# LV25-P_380Vac_ADC.net
KiCad netlist of a schematic drawn in Altium Designer
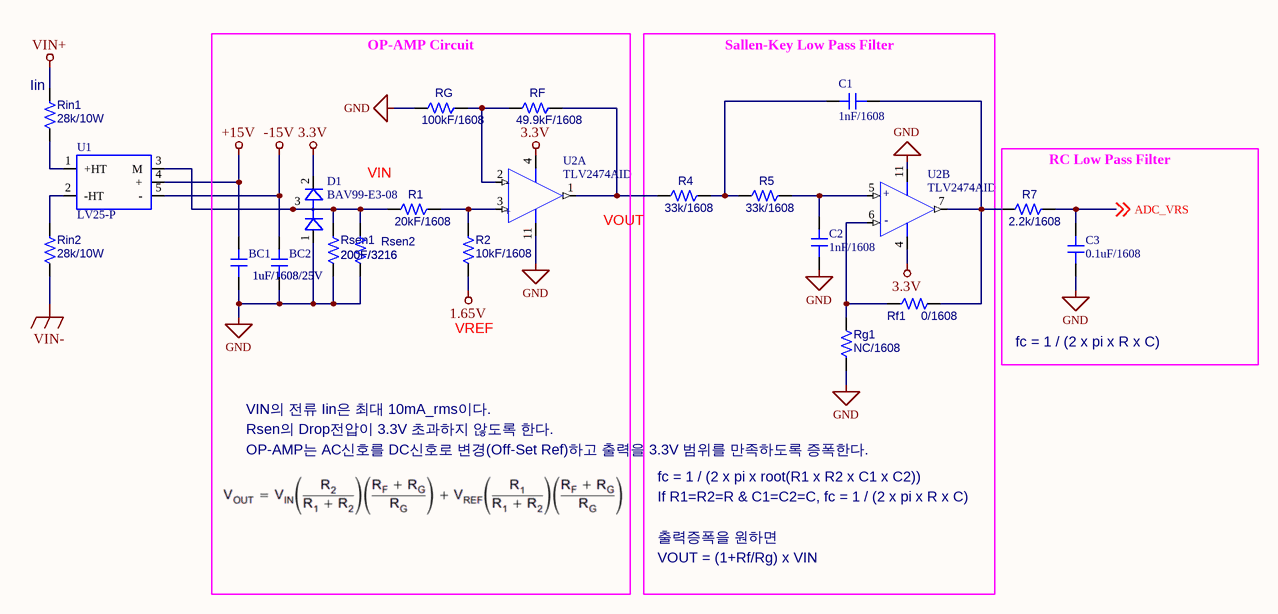
[diagram p0: LV25-P 380Vac ADC 센싱회로.SchDoc]

(export (version "E")
  (design (tool "Eeschema 10.0.6"))
  (components
    (comp (ref "BC1")
      (value "1uF/1608/25V")
      (footprint "C-1608")
      (libsource (lib "*") (part "CAPACITOR NON-POL_1"))
    )
    (comp (ref "BC2")
      (value "1uF/1608/25V")
      (footprint "C-1608")
      (libsource (lib "*") (part "CAPACITOR NON-POL_1"))
    )
    (comp (ref "C1")
      (value "1nF/1608")
      (footprint "C-1608")
      (libsource (lib "*") (part "CAPACITOR NON-POL_1"))
    )
    (comp (ref "C2")
      (value "1nF/1608")
      (footprint "C-1608")
      (libsource (lib "*") (part "CAPACITOR NON-POL_1"))
    )
    (comp (ref "C3")
      (value "0.1uF/1608")
      (footprint "C-1608")
      (libsource (lib "*") (part "CAPACITOR NON-POL_1"))
    )
    (comp (ref "D1")
      (value "BAV99-E3-08")
      (footprint "SOT-23")
      (description "DIODE ARRAY GP 70V 150MA SOT23")
      (libsource (lib "Schlib1_BAV99") (part "BAV99-E3-08"))
    )
    (comp (ref "R1") (value "20kF/1608") (footprint "R-1608") (libsource (lib "*") (part "R_Dup1")))
    (comp (ref "R2") (value "10kF/1608") (footprint "R-1608") (libsource (lib "*") (part "R_Dup1")))
    (comp (ref "R4") (value "33k/1608") (footprint "R-1608") (libsource (lib "*") (part "R_Dup1")))
    (comp (ref "R5") (value "33k/1608") (footprint "R-1608") (libsource (lib "*") (part "R_Dup1")))
    (comp (ref "R7") (value "2.2k/1608") (footprint "R-1608") (libsource (lib "*") (part "R_Dup1")))
    (comp (ref "RF") (value "49.9kF/1608") (footprint "R-1608") (libsource (lib "*") (part "R_Dup1")))
    (comp (ref "Rf1") (value "0/1608") (footprint "R-1608") (libsource (lib "*") (part "R_Dup1")))
    (comp (ref "RG") (value "100kF/1608") (footprint "R-1608") (libsource (lib "*") (part "R_Dup1")))
    (comp (ref "Rg1") (value "NC/1608") (footprint "R-1608") (libsource (lib "*") (part "R_Dup1")))
    (comp (ref "Rin1") (value "28k/10W") (footprint "R-1608") (libsource (lib "*") (part "R_Dup1")))
    (comp (ref "Rin2") (value "28k/10W") (footprint "R-1608") (libsource (lib "*") (part "R_Dup1")))
    (comp (ref "Rsen1") (value "200F/3216") (footprint "R-1608") (libsource (lib "*") (part "R_Dup1")))
    (comp (ref "Rsen2") (value "200F/3216") (footprint "R-1608") (libsource (lib "*") (part "R_Dup1")))
    (comp (ref "U1") (value "LV25-P") (libsource (lib "SysInTeck_SchLib1") (part "LV25-P")))
    (comp (ref "U2") (value "TLV2474AID") (footprint "SO-14") (libsource (lib "*") (part "OPA4336_1")))
  )
  (nets
    (net (code "1") (name "+15V") (class "Default")
      (node (ref "BC1") (pin "1") (pinfunction "1_1") (pintype "passive"))
      (node (ref "U1") (pin "4") (pinfunction "+_4") (pintype "passive"))
    )
    (net (code "2") (name "-15V") (class "Default")
      (node (ref "BC2") (pin "1") (pinfunction "1_1") (pintype "passive"))
      (node (ref "U1") (pin "5") (pinfunction "-_5") (pintype "passive"))
    )
    (net (code "3") (name "1.65V") (class "Default")
      (node (ref "R2") (pin "2") (pinfunction "2_2") (pintype "passive"))
    )
    (net (code "4") (name "3.3V") (class "Default")
      (node (ref "D1") (pin "2") (pinfunction "2_2") (pintype "passive"))
      (node (ref "U2") (pin "4") (pinfunction "+VCC_4") (pintype "power_in"))
    )
    (net (code "5") (name "ADC_VRS") (class "Default")
      (node (ref "C3") (pin "1") (pinfunction "1_1") (pintype "passive"))
      (node (ref "R7") (pin "1") (pinfunction "1_1") (pintype "passive"))
    )
    (net (code "6") (name "GND") (class "Default")
      (node (ref "BC1") (pin "2") (pinfunction "2_2") (pintype "passive"))
      (node (ref "BC2") (pin "2") (pinfunction "2_2") (pintype "passive"))
      (node (ref "C2") (pin "2") (pinfunction "2_2") (pintype "passive"))
      (node (ref "C3") (pin "2") (pinfunction "2_2") (pintype "passive"))
      (node (ref "D1") (pin "1") (pinfunction "1_1") (pintype "passive"))
      (node (ref "RG") (pin "2") (pinfunction "2_2") (pintype "passive"))
      (node (ref "Rg1") (pin "1") (pinfunction "1_1") (pintype "passive"))
      (node (ref "Rsen1") (pin "2") (pinfunction "2_2") (pintype "passive"))
      (node (ref "Rsen2") (pin "2") (pinfunction "2_2") (pintype "passive"))
      (node (ref "U2") (pin "11") (pinfunction "-VCC_11") (pintype "power_in"))
    )
    (net (code "7") (name "Net-(C1-Pad1)") (class "Default")
      (node (ref "C1") (pin "1") (pinfunction "1_1") (pintype "passive"))
      (node (ref "R4") (pin "1") (pinfunction "1_1") (pintype "passive"))
      (node (ref "R5") (pin "2") (pinfunction "2_2") (pintype "passive"))
    )
    (net (code "8") (name "Net-(U1-+HT)") (class "Default")
      (node (ref "Rin1") (pin "2") (pinfunction "2_2") (pintype "passive"))
      (node (ref "U1") (pin "1") (pinfunction "+HT_1") (pintype "passive"))
    )
    (net (code "9") (name "Net-(U1--HT)") (class "Default")
      (node (ref "Rin2") (pin "1") (pinfunction "1_1") (pintype "passive"))
      (node (ref "U1") (pin "2") (pinfunction "-HT_2") (pintype "passive"))
    )
    (net (code "10") (name "Net-(U1-M)") (class "Default")
      (node (ref "D1") (pin "3") (pinfunction "3_3") (pintype "passive"))
      (node (ref "R1") (pin "2") (pinfunction "2_2") (pintype "passive"))
      (node (ref "Rsen1") (pin "1") (pinfunction "1_1") (pintype "passive"))
      (node (ref "Rsen2") (pin "1") (pinfunction "1_1") (pintype "passive"))
      (node (ref "U1") (pin "3") (pinfunction "M_3") (pintype "passive"))
    )
    (net (code "11") (name "Net-(U2A-+IN)") (class "Default")
      (node (ref "R1") (pin "1") (pinfunction "1_1") (pintype "passive"))
      (node (ref "R2") (pin "1") (pinfunction "1_1") (pintype "passive"))
      (node (ref "U2") (pin "3") (pinfunction "+IN_3") (pintype "input"))
    )
    (net (code "12") (name "Net-(U2A--IN)") (class "Default")
      (node (ref "RF") (pin "2") (pinfunction "2_2") (pintype "passive"))
      (node (ref "RG") (pin "1") (pinfunction "1_1") (pintype "passive"))
      (node (ref "U2") (pin "2") (pinfunction "-IN_2") (pintype "input"))
    )
    (net (code "13") (name "Net-(U2A-OUT)") (class "Default")
      (node (ref "R4") (pin "2") (pinfunction "2_2") (pintype "passive"))
      (node (ref "RF") (pin "1") (pinfunction "1_1") (pintype "passive"))
      (node (ref "U2") (pin "1") (pinfunction "OUT_1") (pintype "output"))
    )
    (net (code "14") (name "Net-(U2B-+IN)") (class "Default")
      (node (ref "C2") (pin "1") (pinfunction "1_1") (pintype "passive"))
      (node (ref "R5") (pin "1") (pinfunction "1_1") (pintype "passive"))
      (node (ref "U2") (pin "5") (pinfunction "+IN_5") (pintype "input"))
    )
    (net (code "15") (name "Net-(U2B--IN)") (class "Default")
      (node (ref "Rf1") (pin "1") (pinfunction "1_1") (pintype "passive"))
      (node (ref "Rg1") (pin "2") (pinfunction "2_2") (pintype "passive"))
      (node (ref "U2") (pin "6") (pinfunction "-IN_6") (pintype "input"))
    )
    (net (code "16") (name "Net-(U2B-OUT)") (class "Default")
      (node (ref "C1") (pin "2") (pinfunction "2_2") (pintype "passive"))
      (node (ref "R7") (pin "2") (pinfunction "2_2") (pintype "passive"))
      (node (ref "Rf1") (pin "2") (pinfunction "2_2") (pintype "passive"))
      (node (ref "U2") (pin "7") (pinfunction "OUT_7") (pintype "output"))
    )
    (net (code "17") (name "VIN+") (class "Default")
      (node (ref "Rin1") (pin "1") (pinfunction "1_1") (pintype "passive"))
    )
    (net (code "18") (name "VIN-") (class "Default")
      (node (ref "Rin2") (pin "2") (pinfunction "2_2") (pintype "passive"))
    )
  )
)
